# FindMe_Tag.net
KiCad netlist of a schematic drawn in EAGLE
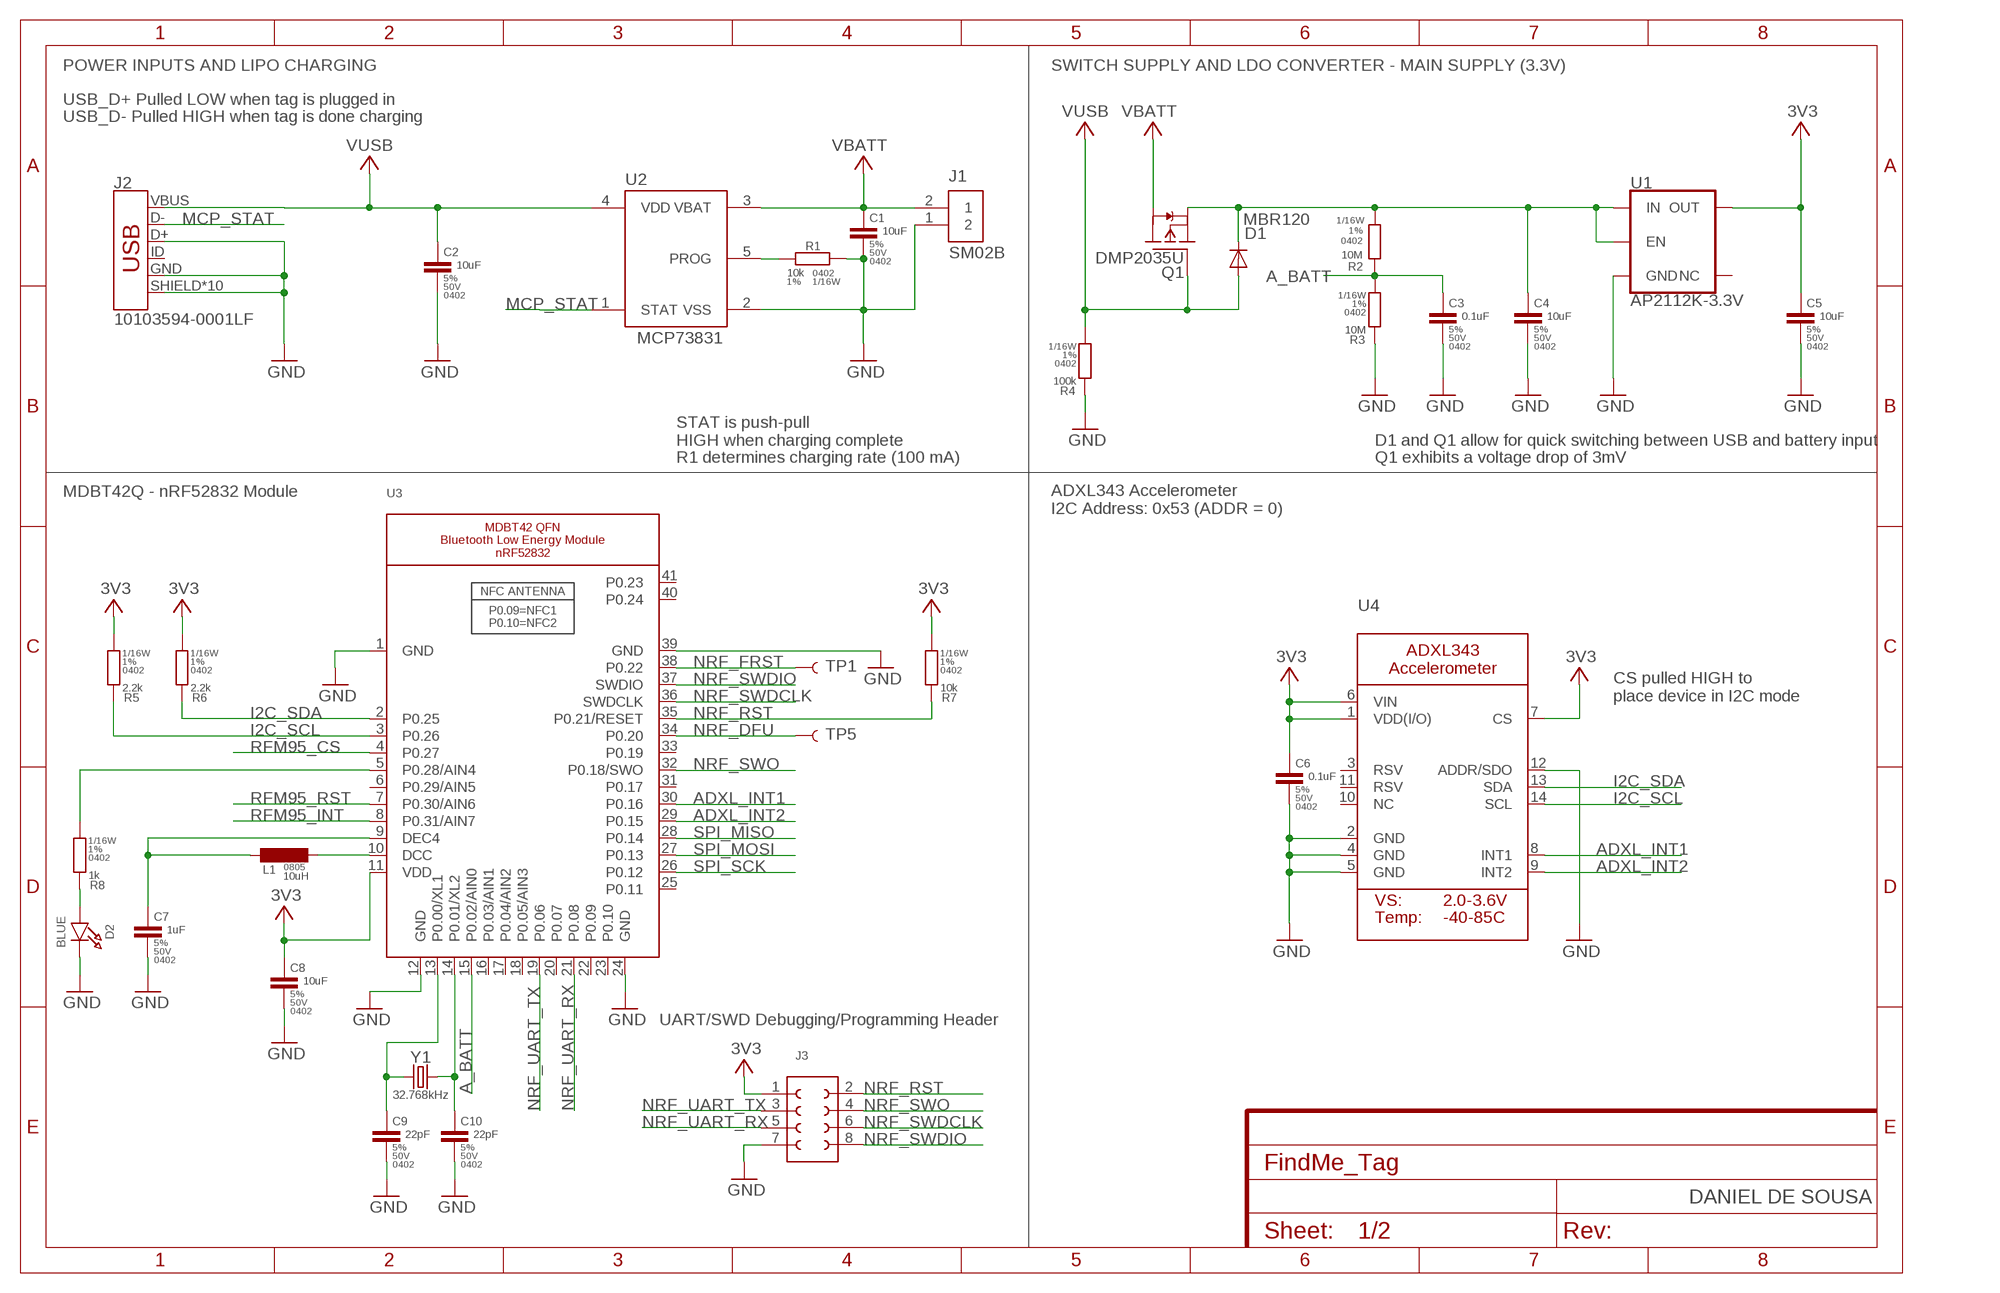
[diagram p0: schematic, sheet 1]
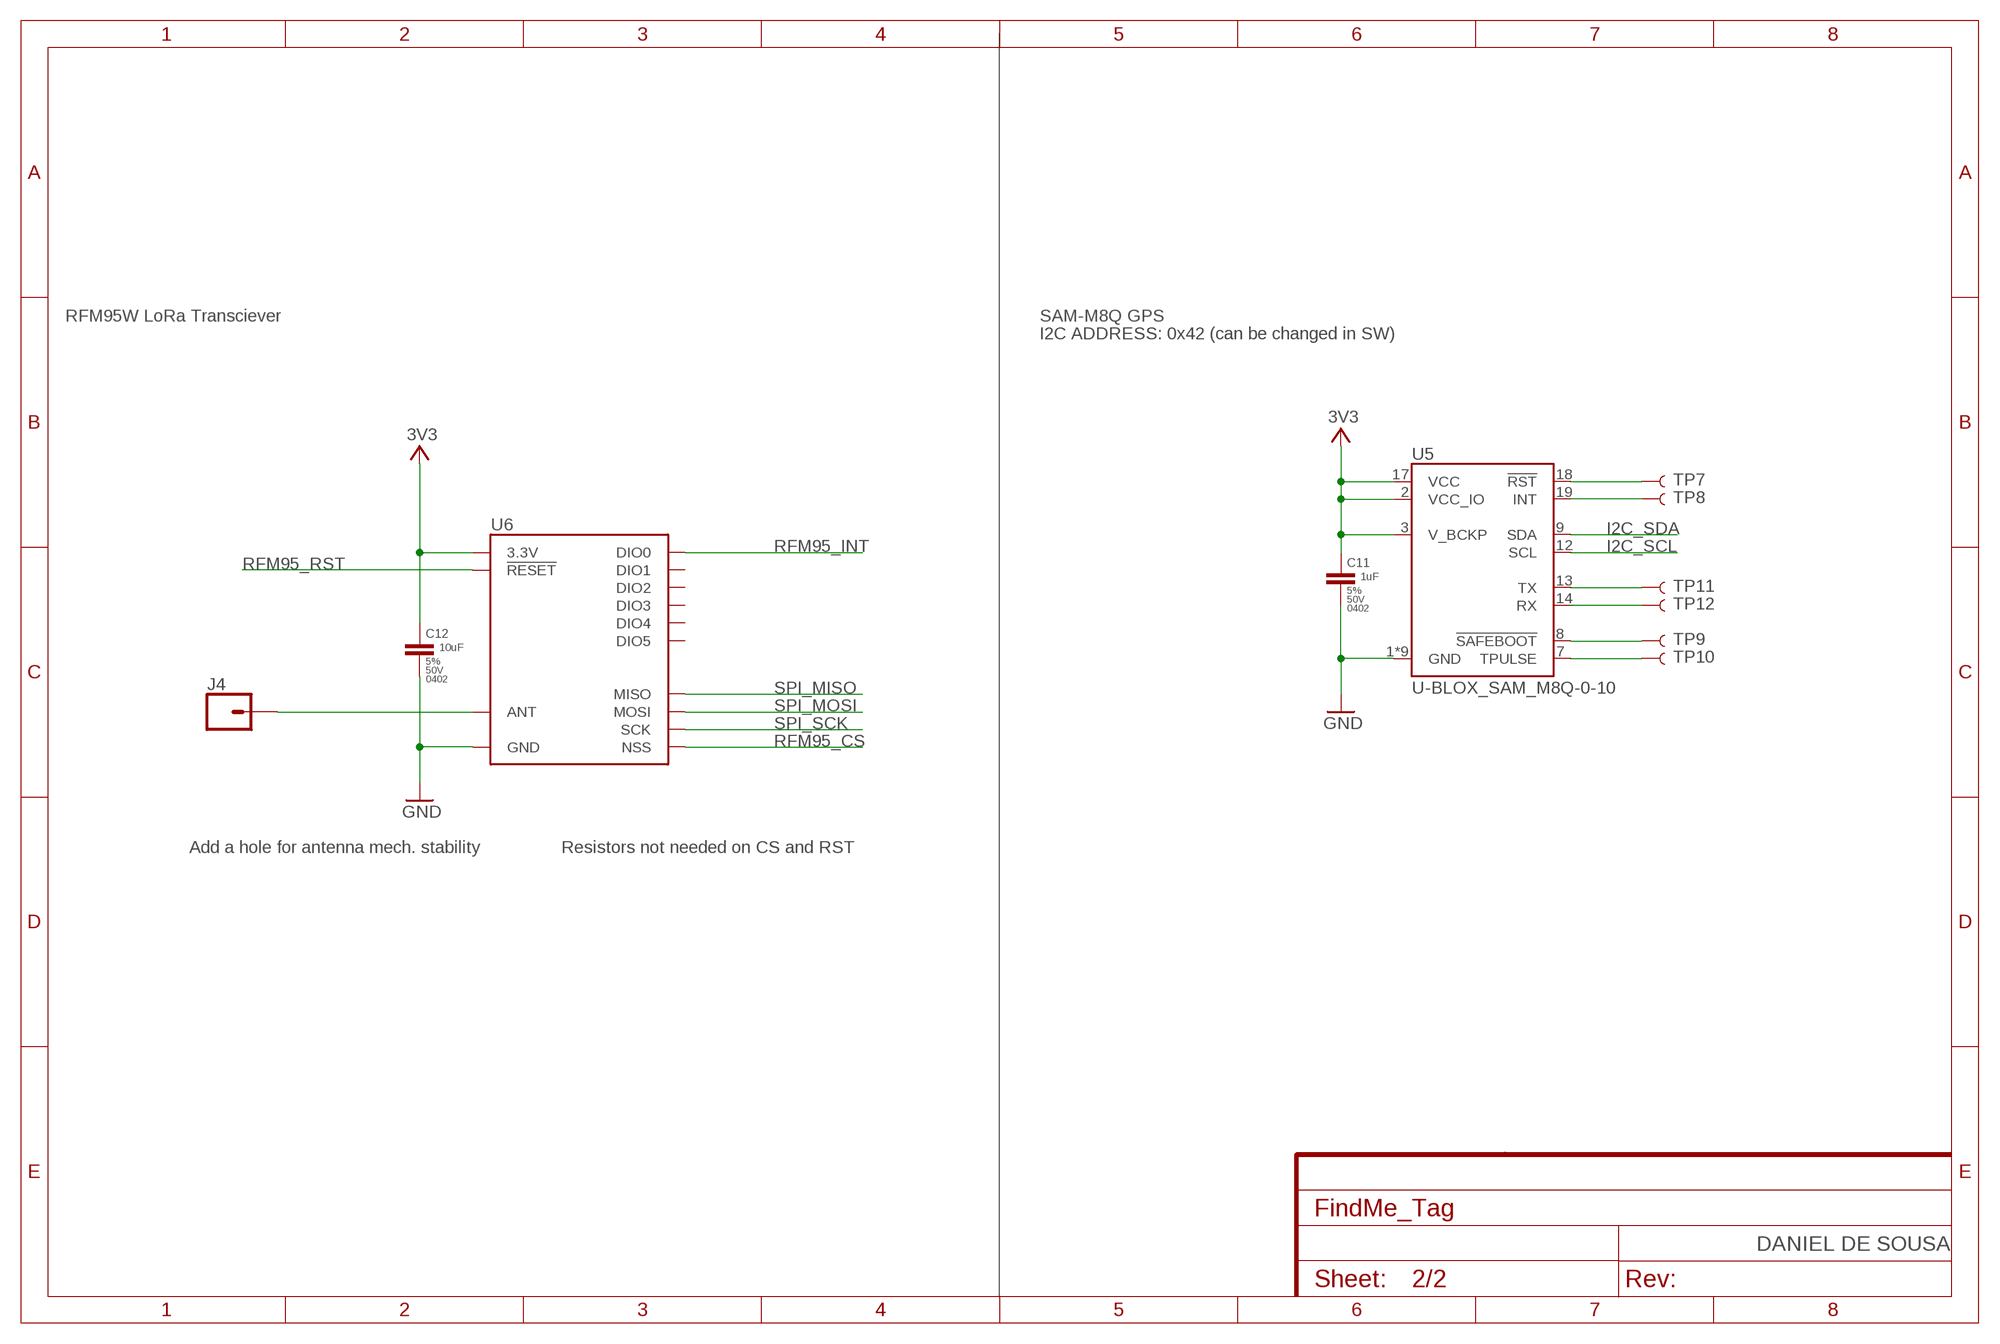
[diagram p1: schematic, sheet 2]

(export (version "E")
  (design (tool "Eeschema 10.0.6"))
  (components
    (comp (ref "C11")
      (value "1uF")
      (footprint "eagle-import:C0402_MURATA_GRM15-GJM15")
      (fields (field (name "TOLERANCE") "5%"))
      (libsource (lib "eagle-import") (part "C-EUC0402_MURATA_GRM15-GJM15"))
    )
    (comp (ref "C12")
      (value "10uF")
      (footprint "eagle-import:C0402_MURATA_GRM15-GJM15")
      (fields (field (name "TOLERANCE") "5%"))
      (libsource (lib "eagle-import") (part "C-EUC0402_MURATA_GRM15-GJM15"))
    )
    (comp (ref "J4")
      (value "CONN_01PTH_NO_SILK_YES_STOP")
      (footprint "eagle-import:1X01_NO_SILK")
      (libsource (lib "eagle-import") (part "CONN_01PTH_NO_SILK_YES_STOP"))
    )
    (comp (ref "TP7")
      (value "TEST-POINT3")
      (footprint "eagle-import:PAD.03X.03")
      (libsource (lib "eagle-import") (part "TEST-POINT3"))
    )
    (comp (ref "TP8")
      (value "TEST-POINT3")
      (footprint "eagle-import:PAD.03X.03")
      (libsource (lib "eagle-import") (part "TEST-POINT3"))
    )
    (comp (ref "TP9")
      (value "TEST-POINT3")
      (footprint "eagle-import:PAD.03X.03")
      (libsource (lib "eagle-import") (part "TEST-POINT3"))
    )
    (comp (ref "TP10")
      (value "TEST-POINT3")
      (footprint "eagle-import:PAD.03X.03")
      (libsource (lib "eagle-import") (part "TEST-POINT3"))
    )
    (comp (ref "TP11")
      (value "TEST-POINT3")
      (footprint "eagle-import:PAD.03X.03")
      (libsource (lib "eagle-import") (part "TEST-POINT3"))
    )
    (comp (ref "TP12")
      (value "TEST-POINT3")
      (footprint "eagle-import:PAD.03X.03")
      (libsource (lib "eagle-import") (part "TEST-POINT3"))
    )
    (comp (ref "U5")
      (value "U-BLOX_SAM_M8Q-0-10")
      (footprint "eagle-import:SAM-M8Q")
      (libsource (lib "eagle-import") (part "U-BLOX_SAM_M8Q-0-10"))
    )
    (comp (ref "U6")
      (value "RFM95W")
      (footprint "eagle-import:RFM95_96_97_98W")
      (libsource (lib "eagle-import") (part "RFM95W"))
    )
    (comp (ref "C1")
      (value "10uF")
      (footprint "eagle-import:C0402_MURATA_GRM15-GJM15")
      (fields (field (name "TOLERANCE") "5%"))
      (libsource (lib "eagle-import") (part "C-EUC0402_MURATA_GRM15-GJM15"))
    )
    (comp (ref "C2")
      (value "10uF")
      (footprint "eagle-import:C0402_MURATA_GRM15-GJM15")
      (fields (field (name "TOLERANCE") "5%"))
      (libsource (lib "eagle-import") (part "C-EUC0402_MURATA_GRM15-GJM15"))
    )
    (comp (ref "C3")
      (value "0.1uF")
      (footprint "eagle-import:C0402_MURATA_GRM15-GJM15")
      (fields (field (name "TOLERANCE") "5%"))
      (libsource (lib "eagle-import") (part "C-EUC0402_MURATA_GRM15-GJM15"))
    )
    (comp (ref "C4")
      (value "10uF")
      (footprint "eagle-import:C0402_MURATA_GRM15-GJM15")
      (fields (field (name "TOLERANCE") "5%"))
      (libsource (lib "eagle-import") (part "C-EUC0402_MURATA_GRM15-GJM15"))
    )
    (comp (ref "C5")
      (value "10uF")
      (footprint "eagle-import:C0402_MURATA_GRM15-GJM15")
      (fields (field (name "TOLERANCE") "5%"))
      (libsource (lib "eagle-import") (part "C-EUC0402_MURATA_GRM15-GJM15"))
    )
    (comp (ref "C6")
      (value "0.1uF")
      (footprint "eagle-import:C0402_MURATA_GRM15-GJM15")
      (fields (field (name "TOLERANCE") "5%"))
      (libsource (lib "eagle-import") (part "C-EUC0402_MURATA_GRM15-GJM15"))
    )
    (comp (ref "C7")
      (value "1uF")
      (footprint "eagle-import:C0402_MURATA_GRM15-GJM15")
      (fields (field (name "TOLERANCE") "5%"))
      (libsource (lib "eagle-import") (part "C-EUC0402_MURATA_GRM15-GJM15"))
    )
    (comp (ref "C8")
      (value "10uF")
      (footprint "eagle-import:C0402_MURATA_GRM15-GJM15")
      (fields (field (name "TOLERANCE") "5%"))
      (libsource (lib "eagle-import") (part "C-EUC0402_MURATA_GRM15-GJM15"))
    )
    (comp (ref "C9")
      (value "22pF")
      (footprint "eagle-import:C0402_MURATA_GRM15-GJM15")
      (fields (field (name "RATING") "50V") (field (name "TOLERANCE") "5%") (field (name "PACKAGE") "0402"))
      (libsource (lib "eagle-import") (part "C-EUC0402_MURATA_GRM15-GJM15"))
    )
    (comp (ref "C10")
      (value "22pF")
      (footprint "eagle-import:C0402_MURATA_GRM15-GJM15")
      (fields (field (name "RATING") "50V") (field (name "TOLERANCE") "5%") (field (name "PACKAGE") "0402"))
      (libsource (lib "eagle-import") (part "C-EUC0402_MURATA_GRM15-GJM15"))
    )
    (comp (ref "D1")
      (value "MBR120")
      (footprint "eagle-import:SOD-123FL")
      (fields (field (name "PARTNO") "AS-ITM-00111"))
      (libsource (lib "eagle-import") (part "AS-ITM-00111"))
    )
    (comp (ref "D2")
      (value "BLUE")
      (footprint "eagle-import:CHIPLED_0805_NOOUTLINE")
      (libsource (lib "eagle-import") (part "LED0805_NOOUTLINE"))
    )
    (comp (ref "J1")
      (value "SM02B")
      (footprint "eagle-import:JST_SH_2X1")
      (fields (field (name "PARTNO") "AS-ITM-00231"))
      (libsource (lib "eagle-import") (part "AS-ITM-00231"))
    )
    (comp (ref "J2")
      (value "10103594-0001LF")
      (footprint "eagle-import:USB-MICROB-PTH-MILL")
      (libsource (lib "eagle-import") (part "USB_MICRO-B_HALF_PTH_MILL"))
    )
    (comp (ref "J3")
      (value "610X08243021")
      (footprint "eagle-import:610X08243021")
      (libsource (lib "eagle-import") (part "610X08243021"))
    )
    (comp (ref "L1")
      (value "10uH")
      (footprint "eagle-import:L0805_MURATA_LQM21")
      (fields (field (name "PACKAGE") "0805") (field (name "TOLERANCE") "20%"))
      (libsource (lib "eagle-import") (part "LQM21PN1R0MC0D"))
    )
    (comp (ref "Q1")
      (value "DMP2035U")
      (footprint "eagle-import:SOT23")
      (fields (field (name "PARTNO") "AS-ITM-00024"))
      (libsource (lib "eagle-import") (part "AS-ITM-00024"))
    )
    (comp (ref "R1")
      (value "10k")
      (footprint "eagle-import:R0402_VISHAY_CRCW0402")
      (fields (field (name "TOLERANCE") "1%") (field (name "RATING") "1/16W") (field (name "PACKAGE") "0402"))
      (libsource (lib "eagle-import") (part "CRCW040210K0FKED"))
    )
    (comp (ref "R2")
      (value "10M")
      (footprint "eagle-import:R0402_VISHAY_CRCW0402")
      (fields (field (name "TOLERANCE") "1%") (field (name "RATING") "1/16W") (field (name "PACKAGE") "0402"))
      (libsource (lib "eagle-import") (part "CRCW04021M00FKED"))
    )
    (comp (ref "R3")
      (value "10M")
      (footprint "eagle-import:R0402_VISHAY_CRCW0402")
      (fields (field (name "TOLERANCE") "1%"))
      (libsource (lib "eagle-import") (part "CRCW04021M00FKED"))
    )
    (comp (ref "R4")
      (value "100k")
      (footprint "eagle-import:R0402_VISHAY_CRCW0402")
      (fields (field (name "TOLERANCE") "1%"))
      (libsource (lib "eagle-import") (part "CRCW04021M00FKED"))
    )
    (comp (ref "R5")
      (value "2.2k")
      (footprint "eagle-import:R0402_VISHAY_CRCW0402")
      (fields (field (name "TOLERANCE") "1%"))
      (libsource (lib "eagle-import") (part "CRCW040210K0FKED"))
    )
    (comp (ref "R6")
      (value "2.2k")
      (footprint "eagle-import:R0402_VISHAY_CRCW0402")
      (fields (field (name "TOLERANCE") "1%"))
      (libsource (lib "eagle-import") (part "CRCW040210K0FKED"))
    )
    (comp (ref "R7")
      (value "10k")
      (footprint "eagle-import:R0402_VISHAY_CRCW0402")
      (fields (field (name "TOLERANCE") "1%"))
      (libsource (lib "eagle-import") (part "CRCW040210K0FKED"))
    )
    (comp (ref "R8")
      (value "1k")
      (footprint "eagle-import:R0402_VISHAY_CRCW0402")
      (fields (field (name "TOLERANCE") "1%"))
      (libsource (lib "eagle-import") (part "CRCW040210K0FKED"))
    )
    (comp (ref "TP1")
      (value "TEST-POINT3")
      (footprint "eagle-import:PAD.03X.03")
      (libsource (lib "eagle-import") (part "TEST-POINT3"))
    )
    (comp (ref "TP5")
      (value "TEST-POINT3")
      (footprint "eagle-import:PAD.03X.03")
      (libsource (lib "eagle-import") (part "TEST-POINT3"))
    )
    (comp (ref "U1")
      (value "AP2112K-3.3V")
      (footprint "eagle-import:SOT23-5")
      (libsource (lib "eagle-import") (part "V_REG_AP2112K-3.3V"))
    )
    (comp (ref "U2")
      (value "MCP73831")
      (footprint "eagle-import:SOT-23")
      (fields (field (name "PARTNO") "AS-ITM-00136"))
      (libsource (lib "eagle-import") (part "AS-ITM-00136"))
    )
    (comp (ref "U3")
      (value "NRF52832_MODULE_MDBT42")
      (footprint "eagle-import:BLE_MODULE_RAYTAC_MDBT42")
      (libsource (lib "eagle-import") (part "NRF52832_MODULE_MDBT42"))
    )
    (comp (ref "U4")
      (value "ACCEL_ADXL343")
      (footprint "eagle-import:LGA14")
      (libsource (lib "eagle-import") (part "ACCEL_ADXL343"))
    )
    (comp (ref "Y1")
      (value "32.768kHz")
      (footprint "eagle-import:CRYSTAL-SMD-3.2X1.5MM")
      (libsource (lib "eagle-import") (part "CRYSTAL-32.768KHZSMD-3.2X1.5"))
    )
  )
  (nets
    (net (code "1") (name "+3V3") (class "Default")
      (node (ref "C11") (pin "1") (pinfunction "1_1") (pintype "passive"))
      (node (ref "C12") (pin "1") (pinfunction "1_1") (pintype "passive"))
      (node (ref "C5") (pin "1") (pinfunction "1_1") (pintype "passive"))
      (node (ref "C6") (pin "1") (pinfunction "1_1") (pintype "passive"))
      (node (ref "C8") (pin "1") (pinfunction "1_1") (pintype "passive"))
      (node (ref "J3") (pin "1") (pinfunction "1_1") (pintype "passive"))
      (node (ref "R5") (pin "2") (pinfunction "2_2") (pintype "passive"))
      (node (ref "R6") (pin "2") (pinfunction "2_2") (pintype "passive"))
      (node (ref "R7") (pin "2") (pinfunction "2_2") (pintype "passive"))
      (node (ref "U1") (pin "5") (pinfunction "OUT_5") (pintype "passive"))
      (node (ref "U3") (pin "11") (pinfunction "VDD_11") (pintype "bidirectional"))
      (node (ref "U4") (pin "1") (pinfunction "VDD(I/O)_1") (pintype "bidirectional"))
      (node (ref "U4") (pin "6") (pinfunction "VIN_6") (pintype "bidirectional"))
      (node (ref "U4") (pin "7") (pinfunction "CS_7") (pintype "bidirectional"))
      (node (ref "U5") (pin "17") (pinfunction "VCC_17") (pintype "bidirectional"))
      (node (ref "U5") (pin "2") (pinfunction "VCC_IO_2") (pintype "bidirectional"))
      (node (ref "U5") (pin "3") (pinfunction "V_BCKP_3") (pintype "bidirectional"))
      (node (ref "U6") (pin "3.3V") (pinfunction "3.3V_3.3V") (pintype "bidirectional"))
    )
    (net (code "2") (name "ADXL_INT1") (class "Default")
      (node (ref "U3") (pin "30") (pinfunction "P0.16_30") (pintype "bidirectional"))
      (node (ref "U4") (pin "8") (pinfunction "INT1_8") (pintype "bidirectional"))
    )
    (net (code "3") (name "ADXL_INT2") (class "Default")
      (node (ref "U3") (pin "29") (pinfunction "P0.15_29") (pintype "bidirectional"))
      (node (ref "U4") (pin "9") (pinfunction "INT2_9") (pintype "bidirectional"))
    )
    (net (code "4") (name "A_BATT") (class "Default")
      (node (ref "C3") (pin "1") (pinfunction "1_1") (pintype "passive"))
      (node (ref "R2") (pin "1") (pinfunction "1_1") (pintype "passive"))
      (node (ref "R3") (pin "2") (pinfunction "2_2") (pintype "passive"))
      (node (ref "U3") (pin "15") (pinfunction "P0.02/AIN0_15") (pintype "bidirectional"))
    )
    (net (code "5") (name "GND") (class "Default")
      (node (ref "C1") (pin "2") (pinfunction "2_2") (pintype "passive"))
      (node (ref "C10") (pin "2") (pinfunction "2_2") (pintype "passive"))
      (node (ref "C11") (pin "2") (pinfunction "2_2") (pintype "passive"))
      (node (ref "C12") (pin "2") (pinfunction "2_2") (pintype "passive"))
      (node (ref "C2") (pin "2") (pinfunction "2_2") (pintype "passive"))
      (node (ref "C3") (pin "2") (pinfunction "2_2") (pintype "passive"))
      (node (ref "C4") (pin "2") (pinfunction "2_2") (pintype "passive"))
      (node (ref "C5") (pin "2") (pinfunction "2_2") (pintype "passive"))
      (node (ref "C6") (pin "2") (pinfunction "2_2") (pintype "passive"))
      (node (ref "C7") (pin "2") (pinfunction "2_2") (pintype "passive"))
      (node (ref "C8") (pin "2") (pinfunction "2_2") (pintype "passive"))
      (node (ref "C9") (pin "2") (pinfunction "2_2") (pintype "passive"))
      (node (ref "D2") (pin "C") (pinfunction "C_C") (pintype "passive"))
      (node (ref "J1") (pin "1") (pinfunction "2_1") (pintype "bidirectional"))
      (node (ref "J2") (pin "D+") (pinfunction "D+_D+") (pintype "bidirectional"))
      (node (ref "J2") (pin "GND") (pinfunction "GND_GND") (pintype "power_in"))
      (node (ref "J2") (pin "SHIELD") (pinfunction "SHIELD_SHIELD") (pintype "bidirectional"))
      (node (ref "J2") (pin "SHIELD10") (pinfunction "SHIELD_SHIELD10") (pintype "bidirectional"))
      (node (ref "J2") (pin "SHIELD2") (pinfunction "SHIELD_SHIELD2") (pintype "bidirectional"))
      (node (ref "J2") (pin "SHIELD3") (pinfunction "SHIELD_SHIELD3") (pintype "bidirectional"))
      (node (ref "J2") (pin "SHIELD4") (pinfunction "SHIELD_SHIELD4") (pintype "bidirectional"))
      (node (ref "J2") (pin "SHIELD5") (pinfunction "SHIELD_SHIELD5") (pintype "bidirectional"))
      (node (ref "J2") (pin "SHIELD6") (pinfunction "SHIELD_SHIELD6") (pintype "bidirectional"))
      (node (ref "J2") (pin "SHIELD7") (pinfunction "SHIELD_SHIELD7") (pintype "bidirectional"))
      (node (ref "J2") (pin "SHIELD8") (pinfunction "SHIELD_SHIELD8") (pintype "bidirectional"))
      (node (ref "J2") (pin "SHIELD9") (pinfunction "SHIELD_SHIELD9") (pintype "bidirectional"))
      (node (ref "J3") (pin "7") (pinfunction "4_7") (pintype "passive"))
      (node (ref "R1") (pin "1") (pinfunction "1_1") (pintype "passive"))
      (node (ref "R3") (pin "1") (pinfunction "1_1") (pintype "passive"))
      (node (ref "R4") (pin "1") (pinfunction "1_1") (pintype "passive"))
      (node (ref "U1") (pin "2") (pinfunction "GND_2") (pintype "input"))
      (node (ref "U2") (pin "2") (pinfunction "VSS_2") (pintype "bidirectional"))
      (node (ref "U3") (pin "1") (pinfunction "GND_1") (pintype "bidirectional"))
      (node (ref "U3") (pin "12") (pinfunction "GND_12") (pintype "bidirectional"))
      (node (ref "U3") (pin "24") (pinfunction "GND_24") (pintype "bidirectional"))
      (node (ref "U3") (pin "39") (pinfunction "GND_39") (pintype "bidirectional"))
      (node (ref "U4") (pin "12") (pinfunction "ADDR/SDO_12") (pintype "bidirectional"))
      (node (ref "U4") (pin "2") (pinfunction "GND_2") (pintype "bidirectional"))
      (node (ref "U4") (pin "4") (pinfunction "GND_4") (pintype "bidirectional"))
      (node (ref "U4") (pin "5") (pinfunction "GND_5") (pintype "bidirectional"))
      (node (ref "U5") (pin "1") (pinfunction "GND_1") (pintype "bidirectional"))
      (node (ref "U5") (pin "10") (pinfunction "GND_10") (pintype "bidirectional"))
      (node (ref "U5") (pin "11") (pinfunction "GND_11") (pintype "bidirectional"))
      (node (ref "U5") (pin "15") (pinfunction "GND_15") (pintype "bidirectional"))
      (node (ref "U5") (pin "16") (pinfunction "GND_16") (pintype "bidirectional"))
      (node (ref "U5") (pin "20") (pinfunction "GND_20") (pintype "bidirectional"))
      (node (ref "U5") (pin "4") (pinfunction "GND_4") (pintype "bidirectional"))
      (node (ref "U5") (pin "5") (pinfunction "GND_5") (pintype "bidirectional"))
      (node (ref "U5") (pin "6") (pinfunction "GND_6") (pintype "bidirectional"))
      (node (ref "U6") (pin "GND@1") (pinfunction "GND_GND@1") (pintype "bidirectional"))
      (node (ref "U6") (pin "GND@2") (pinfunction "GND_GND@2") (pintype "bidirectional"))
      (node (ref "U6") (pin "GND@3") (pinfunction "GND_GND@3") (pintype "bidirectional"))
    )
    (net (code "6") (name "I2C_SCL") (class "Default")
      (node (ref "R5") (pin "1") (pinfunction "1_1") (pintype "passive"))
      (node (ref "U3") (pin "3") (pinfunction "P0.26_3") (pintype "bidirectional"))
      (node (ref "U4") (pin "14") (pinfunction "SCL_14") (pintype "bidirectional"))
      (node (ref "U5") (pin "12") (pinfunction "SCL_12") (pintype "bidirectional"))
    )
    (net (code "7") (name "I2C_SDA") (class "Default")
      (node (ref "R6") (pin "1") (pinfunction "1_1") (pintype "passive"))
      (node (ref "U3") (pin "2") (pinfunction "P0.25_2") (pintype "bidirectional"))
      (node (ref "U4") (pin "13") (pinfunction "SDA_13") (pintype "bidirectional"))
      (node (ref "U5") (pin "9") (pinfunction "SDA_9") (pintype "bidirectional"))
    )
    (net (code "8") (name "MCP_STAT") (class "Default")
      (node (ref "J2") (pin "D-") (pinfunction "D-_D-") (pintype "bidirectional"))
      (node (ref "U2") (pin "1") (pinfunction "STAT_1") (pintype "bidirectional"))
    )
    (net (code "9") (name "NRF_DFU") (class "Default")
      (node (ref "TP5") (pin "P$1") (pinfunction "1_P$1") (pintype "bidirectional"))
      (node (ref "U3") (pin "34") (pinfunction "P0.20_34") (pintype "bidirectional"))
    )
    (net (code "10") (name "NRF_FRST") (class "Default")
      (node (ref "TP1") (pin "P$1") (pinfunction "1_P$1") (pintype "bidirectional"))
      (node (ref "U3") (pin "38") (pinfunction "P0.22_38") (pintype "bidirectional"))
    )
    (net (code "11") (name "NRF_RST") (class "Default")
      (node (ref "J3") (pin "2") (pinfunction "8_2") (pintype "passive"))
      (node (ref "R7") (pin "1") (pinfunction "1_1") (pintype "passive"))
      (node (ref "U3") (pin "35") (pinfunction "P0.21/RESET_35") (pintype "bidirectional"))
    )
    (net (code "12") (name "NRF_SWDCLK") (class "Default")
      (node (ref "J3") (pin "6") (pinfunction "6_6") (pintype "passive"))
      (node (ref "U3") (pin "36") (pinfunction "SWDCLK_36") (pintype "bidirectional"))
    )
    (net (code "13") (name "NRF_SWDIO") (class "Default")
      (node (ref "J3") (pin "8") (pinfunction "5_8") (pintype "passive"))
      (node (ref "U3") (pin "37") (pinfunction "SWDIO_37") (pintype "bidirectional"))
    )
    (net (code "14") (name "NRF_SWO") (class "Default")
      (node (ref "J3") (pin "4") (pinfunction "7_4") (pintype "passive"))
      (node (ref "U3") (pin "32") (pinfunction "P0.18/SWO_32") (pintype "bidirectional"))
    )
    (net (code "15") (name "NRF_UART_RX") (class "Default")
      (node (ref "J3") (pin "5") (pinfunction "3_5") (pintype "passive"))
      (node (ref "U3") (pin "21") (pinfunction "P0.08_21") (pintype "bidirectional"))
    )
    (net (code "16") (name "NRF_UART_TX") (class "Default")
      (node (ref "J3") (pin "3") (pinfunction "2_3") (pintype "passive"))
      (node (ref "U3") (pin "19") (pinfunction "P0.06_19") (pintype "bidirectional"))
    )
    (net (code "17") (name "Net-(D2-PadA)") (class "Default")
      (node (ref "D2") (pin "A") (pinfunction "A_A") (pintype "passive"))
      (node (ref "R8") (pin "1") (pinfunction "1_1") (pintype "passive"))
    )
    (net (code "18") (name "Net-(J4-Pad1)") (class "Default")
      (node (ref "J4") (pin "1") (pinfunction "1_1") (pintype "passive"))
      (node (ref "U6") (pin "ANT") (pinfunction "ANT_ANT") (pintype "bidirectional"))
    )
    (net (code "19") (name "Net-(L1-1)") (class "Default")
      (node (ref "C7") (pin "1") (pinfunction "1_1") (pintype "passive"))
      (node (ref "L1") (pin "P$1") (pinfunction "1_P$1") (pintype "passive"))
      (node (ref "U3") (pin "9") (pinfunction "DEC4_9") (pintype "bidirectional"))
    )
    (net (code "20") (name "Net-(L1-2)") (class "Default")
      (node (ref "L1") (pin "P$2") (pinfunction "2_P$2") (pintype "passive"))
      (node (ref "U3") (pin "10") (pinfunction "DCC_10") (pintype "bidirectional"))
    )
    (net (code "21") (name "Net-(Q1-S)") (class "Default")
      (node (ref "C4") (pin "1") (pinfunction "1_1") (pintype "passive"))
      (node (ref "D1") (pin "C") (pinfunction "C_C") (pintype "passive"))
      (node (ref "Q1") (pin "E") (pinfunction "S_E") (pintype "passive"))
      (node (ref "R2") (pin "2") (pinfunction "2_2") (pintype "passive"))
      (node (ref "U1") (pin "1") (pinfunction "IN_1") (pintype "input"))
      (node (ref "U1") (pin "3") (pinfunction "EN_3") (pintype "input"))
    )
    (net (code "22") (name "Net-(TP7-1)") (class "Default")
      (node (ref "TP7") (pin "P$1") (pinfunction "1_P$1") (pintype "bidirectional"))
      (node (ref "U5") (pin "18") (pinfunction "~{RST}_18") (pintype "bidirectional"))
    )
    (net (code "23") (name "Net-(TP8-1)") (class "Default")
      (node (ref "TP8") (pin "P$1") (pinfunction "1_P$1") (pintype "bidirectional"))
      (node (ref "U5") (pin "19") (pinfunction "INT_19") (pintype "bidirectional"))
    )
    (net (code "24") (name "Net-(TP9-1)") (class "Default")
      (node (ref "TP9") (pin "P$1") (pinfunction "1_P$1") (pintype "bidirectional"))
      (node (ref "U5") (pin "8") (pinfunction "~{SAFEBOOT}_8") (pintype "bidirectional"))
    )
    (net (code "25") (name "Net-(TP10-1)") (class "Default")
      (node (ref "TP10") (pin "P$1") (pinfunction "1_P$1") (pintype "bidirectional"))
      (node (ref "U5") (pin "7") (pinfunction "TPULSE_7") (pintype "bidirectional"))
    )
    (net (code "26") (name "Net-(TP11-1)") (class "Default")
      (node (ref "TP11") (pin "P$1") (pinfunction "1_P$1") (pintype "bidirectional"))
      (node (ref "U5") (pin "13") (pinfunction "TX_13") (pintype "bidirectional"))
    )
    (net (code "27") (name "Net-(TP12-1)") (class "Default")
      (node (ref "TP12") (pin "P$1") (pinfunction "1_P$1") (pintype "bidirectional"))
      (node (ref "U5") (pin "14") (pinfunction "RX_14") (pintype "bidirectional"))
    )
    (net (code "28") (name "Net-(U2-PROG)") (class "Default")
      (node (ref "R1") (pin "2") (pinfunction "2_2") (pintype "passive"))
      (node (ref "U2") (pin "5") (pinfunction "PROG_5") (pintype "bidirectional"))
    )
    (net (code "29") (name "Net-(U3-P0.00{slash}XL1)") (class "Default")
      (node (ref "C9") (pin "1") (pinfunction "1_1") (pintype "passive"))
      (node (ref "U3") (pin "13") (pinfunction "P0.00/XL1_13") (pintype "bidirectional"))
      (node (ref "Y1") (pin "P$1") (pinfunction "1_P$1") (pintype "passive"))
    )
    (net (code "30") (name "Net-(U3-P0.01{slash}XL2)") (class "Default")
      (node (ref "C10") (pin "1") (pinfunction "1_1") (pintype "passive"))
      (node (ref "U3") (pin "14") (pinfunction "P0.01/XL2_14") (pintype "bidirectional"))
      (node (ref "Y1") (pin "P$2") (pinfunction "2_P$2") (pintype "passive"))
    )
    (net (code "31") (name "Net-(U3-P0.28{slash}AIN4)") (class "Default")
      (node (ref "R8") (pin "2") (pinfunction "2_2") (pintype "passive"))
      (node (ref "U3") (pin "5") (pinfunction "P0.28/AIN4_5") (pintype "bidirectional"))
    )
    (net (code "32") (name "RFM95_CS") (class "Default")
      (node (ref "U3") (pin "4") (pinfunction "P0.27_4") (pintype "bidirectional"))
      (node (ref "U6") (pin "NSS") (pinfunction "NSS_NSS") (pintype "bidirectional"))
    )
    (net (code "33") (name "RFM95_INT") (class "Default")
      (node (ref "U3") (pin "8") (pinfunction "P0.31/AIN7_8") (pintype "bidirectional"))
      (node (ref "U6") (pin "DIO0") (pinfunction "DIO0_DIO0") (pintype "bidirectional"))
    )
    (net (code "34") (name "RFM95_RST") (class "Default")
      (node (ref "U3") (pin "7") (pinfunction "P0.30/AIN6_7") (pintype "bidirectional"))
      (node (ref "U6") (pin "!RESET") (pinfunction "~{RESET}_!RESET") (pintype "bidirectional"))
    )
    (net (code "35") (name "SPI_MISO") (class "Default")
      (node (ref "U3") (pin "28") (pinfunction "P0.14_28") (pintype "bidirectional"))
      (node (ref "U6") (pin "MISO") (pinfunction "MISO_MISO") (pintype "bidirectional"))
    )
    (net (code "36") (name "SPI_MOSI") (class "Default")
      (node (ref "U3") (pin "27") (pinfunction "P0.13_27") (pintype "bidirectional"))
      (node (ref "U6") (pin "MOSI") (pinfunction "MOSI_MOSI") (pintype "bidirectional"))
    )
    (net (code "37") (name "SPI_SCK") (class "Default")
      (node (ref "U3") (pin "26") (pinfunction "P0.12_26") (pintype "bidirectional"))
      (node (ref "U6") (pin "SCK") (pinfunction "SCK_SCK") (pintype "bidirectional"))
    )
    (net (code "38") (name "VBATT") (class "Default")
      (node (ref "C1") (pin "1") (pinfunction "1_1") (pintype "passive"))
      (node (ref "J1") (pin "2") (pinfunction "1_2") (pintype "bidirectional"))
      (node (ref "Q1") (pin "C") (pinfunction "D_C") (pintype "passive"))
      (node (ref "U2") (pin "3") (pinfunction "VBAT_3") (pintype "bidirectional"))
    )
    (net (code "39") (name "VUSB") (class "Default")
      (node (ref "C2") (pin "1") (pinfunction "1_1") (pintype "passive"))
      (node (ref "D1") (pin "A") (pinfunction "A_A") (pintype "passive"))
      (node (ref "J2") (pin "VBUS") (pinfunction "VBUS_VBUS") (pintype "power_in"))
      (node (ref "Q1") (pin "B") (pinfunction "G_B") (pintype "passive"))
      (node (ref "R4") (pin "2") (pinfunction "2_2") (pintype "passive"))
      (node (ref "U2") (pin "4") (pinfunction "VDD_4") (pintype "bidirectional"))
    )
    (net (code "40") (name "unconnected-(J2-PadID)") (class "Default")
      (node (ref "J2") (pin "ID") (pinfunction "ID_ID") (pintype "bidirectional"))
    )
    (net (code "41") (name "unconnected-(U1-NC-Pad4)") (class "Default")
      (node (ref "U1") (pin "4") (pinfunction "NC_4") (pintype "no_connect"))
    )
    (net (code "42") (name "unconnected-(U3-P0.03{slash}AIN1-Pad16)") (class "Default")
      (node (ref "U3") (pin "16") (pinfunction "P0.03/AIN1_16") (pintype "bidirectional"))
    )
    (net (code "43") (name "unconnected-(U3-P0.04{slash}AIN2-Pad17)") (class "Default")
      (node (ref "U3") (pin "17") (pinfunction "P0.04/AIN2_17") (pintype "bidirectional"))
    )
    (net (code "44") (name "unconnected-(U3-P0.05{slash}AIN3-Pad18)") (class "Default")
      (node (ref "U3") (pin "18") (pinfunction "P0.05/AIN3_18") (pintype "bidirectional"))
    )
    (net (code "45") (name "unconnected-(U3-P0.07-Pad20)") (class "Default")
      (node (ref "U3") (pin "20") (pinfunction "P0.07_20") (pintype "bidirectional"))
    )
    (net (code "46") (name "unconnected-(U3-P0.09-Pad22)") (class "Default")
      (node (ref "U3") (pin "22") (pinfunction "P0.09_22") (pintype "bidirectional"))
    )
    (net (code "47") (name "unconnected-(U3-P0.10-Pad23)") (class "Default")
      (node (ref "U3") (pin "23") (pinfunction "P0.10_23") (pintype "bidirectional"))
    )
    (net (code "48") (name "unconnected-(U3-P0.11-Pad25)") (class "Default")
      (node (ref "U3") (pin "25") (pinfunction "P0.11_25") (pintype "bidirectional"))
    )
    (net (code "49") (name "unconnected-(U3-P0.17-Pad31)") (class "Default")
      (node (ref "U3") (pin "31") (pinfunction "P0.17_31") (pintype "bidirectional"))
    )
    (net (code "50") (name "unconnected-(U3-P0.19-Pad33)") (class "Default")
      (node (ref "U3") (pin "33") (pinfunction "P0.19_33") (pintype "bidirectional"))
    )
    (net (code "51") (name "unconnected-(U3-P0.23-Pad41)") (class "Default")
      (node (ref "U3") (pin "41") (pinfunction "P0.23_41") (pintype "bidirectional"))
    )
    (net (code "52") (name "unconnected-(U3-P0.24-Pad40)") (class "Default")
      (node (ref "U3") (pin "40") (pinfunction "P0.24_40") (pintype "bidirectional"))
    )
    (net (code "53") (name "unconnected-(U3-P0.29{slash}AIN5-Pad6)") (class "Default")
      (node (ref "U3") (pin "6") (pinfunction "P0.29/AIN5_6") (pintype "bidirectional"))
    )
    (net (code "54") (name "unconnected-(U4-NC-Pad10)") (class "Default")
      (node (ref "U4") (pin "10") (pinfunction "NC_10") (pintype "bidirectional"))
    )
    (net (code "55") (name "unconnected-(U4-RSV-Pad3)") (class "Default")
      (node (ref "U4") (pin "3") (pinfunction "RSV_3") (pintype "bidirectional"))
    )
    (net (code "56") (name "unconnected-(U4-RSV-Pad11)") (class "Default")
      (node (ref "U4") (pin "11") (pinfunction "RSV_11") (pintype "bidirectional"))
    )
    (net (code "57") (name "unconnected-(U6-PadDIO1)") (class "Default")
      (node (ref "U6") (pin "DIO1") (pinfunction "DIO1_DIO1") (pintype "bidirectional"))
    )
    (net (code "58") (name "unconnected-(U6-PadDIO2)") (class "Default")
      (node (ref "U6") (pin "DIO2") (pinfunction "DIO2_DIO2") (pintype "bidirectional"))
    )
    (net (code "59") (name "unconnected-(U6-PadDIO3)") (class "Default")
      (node (ref "U6") (pin "DIO3") (pinfunction "DIO3_DIO3") (pintype "bidirectional"))
    )
    (net (code "60") (name "unconnected-(U6-PadDIO4)") (class "Default")
      (node (ref "U6") (pin "DIO4") (pinfunction "DIO4_DIO4") (pintype "bidirectional"))
    )
    (net (code "61") (name "unconnected-(U6-PadDIO5)") (class "Default")
      (node (ref "U6") (pin "DIO5") (pinfunction "DIO5_DIO5") (pintype "bidirectional"))
    )
  )
)
